# SCH_RFID-esp32-design_2024-09-27.net
KiCad netlist of a schematic drawn in EasyEDA
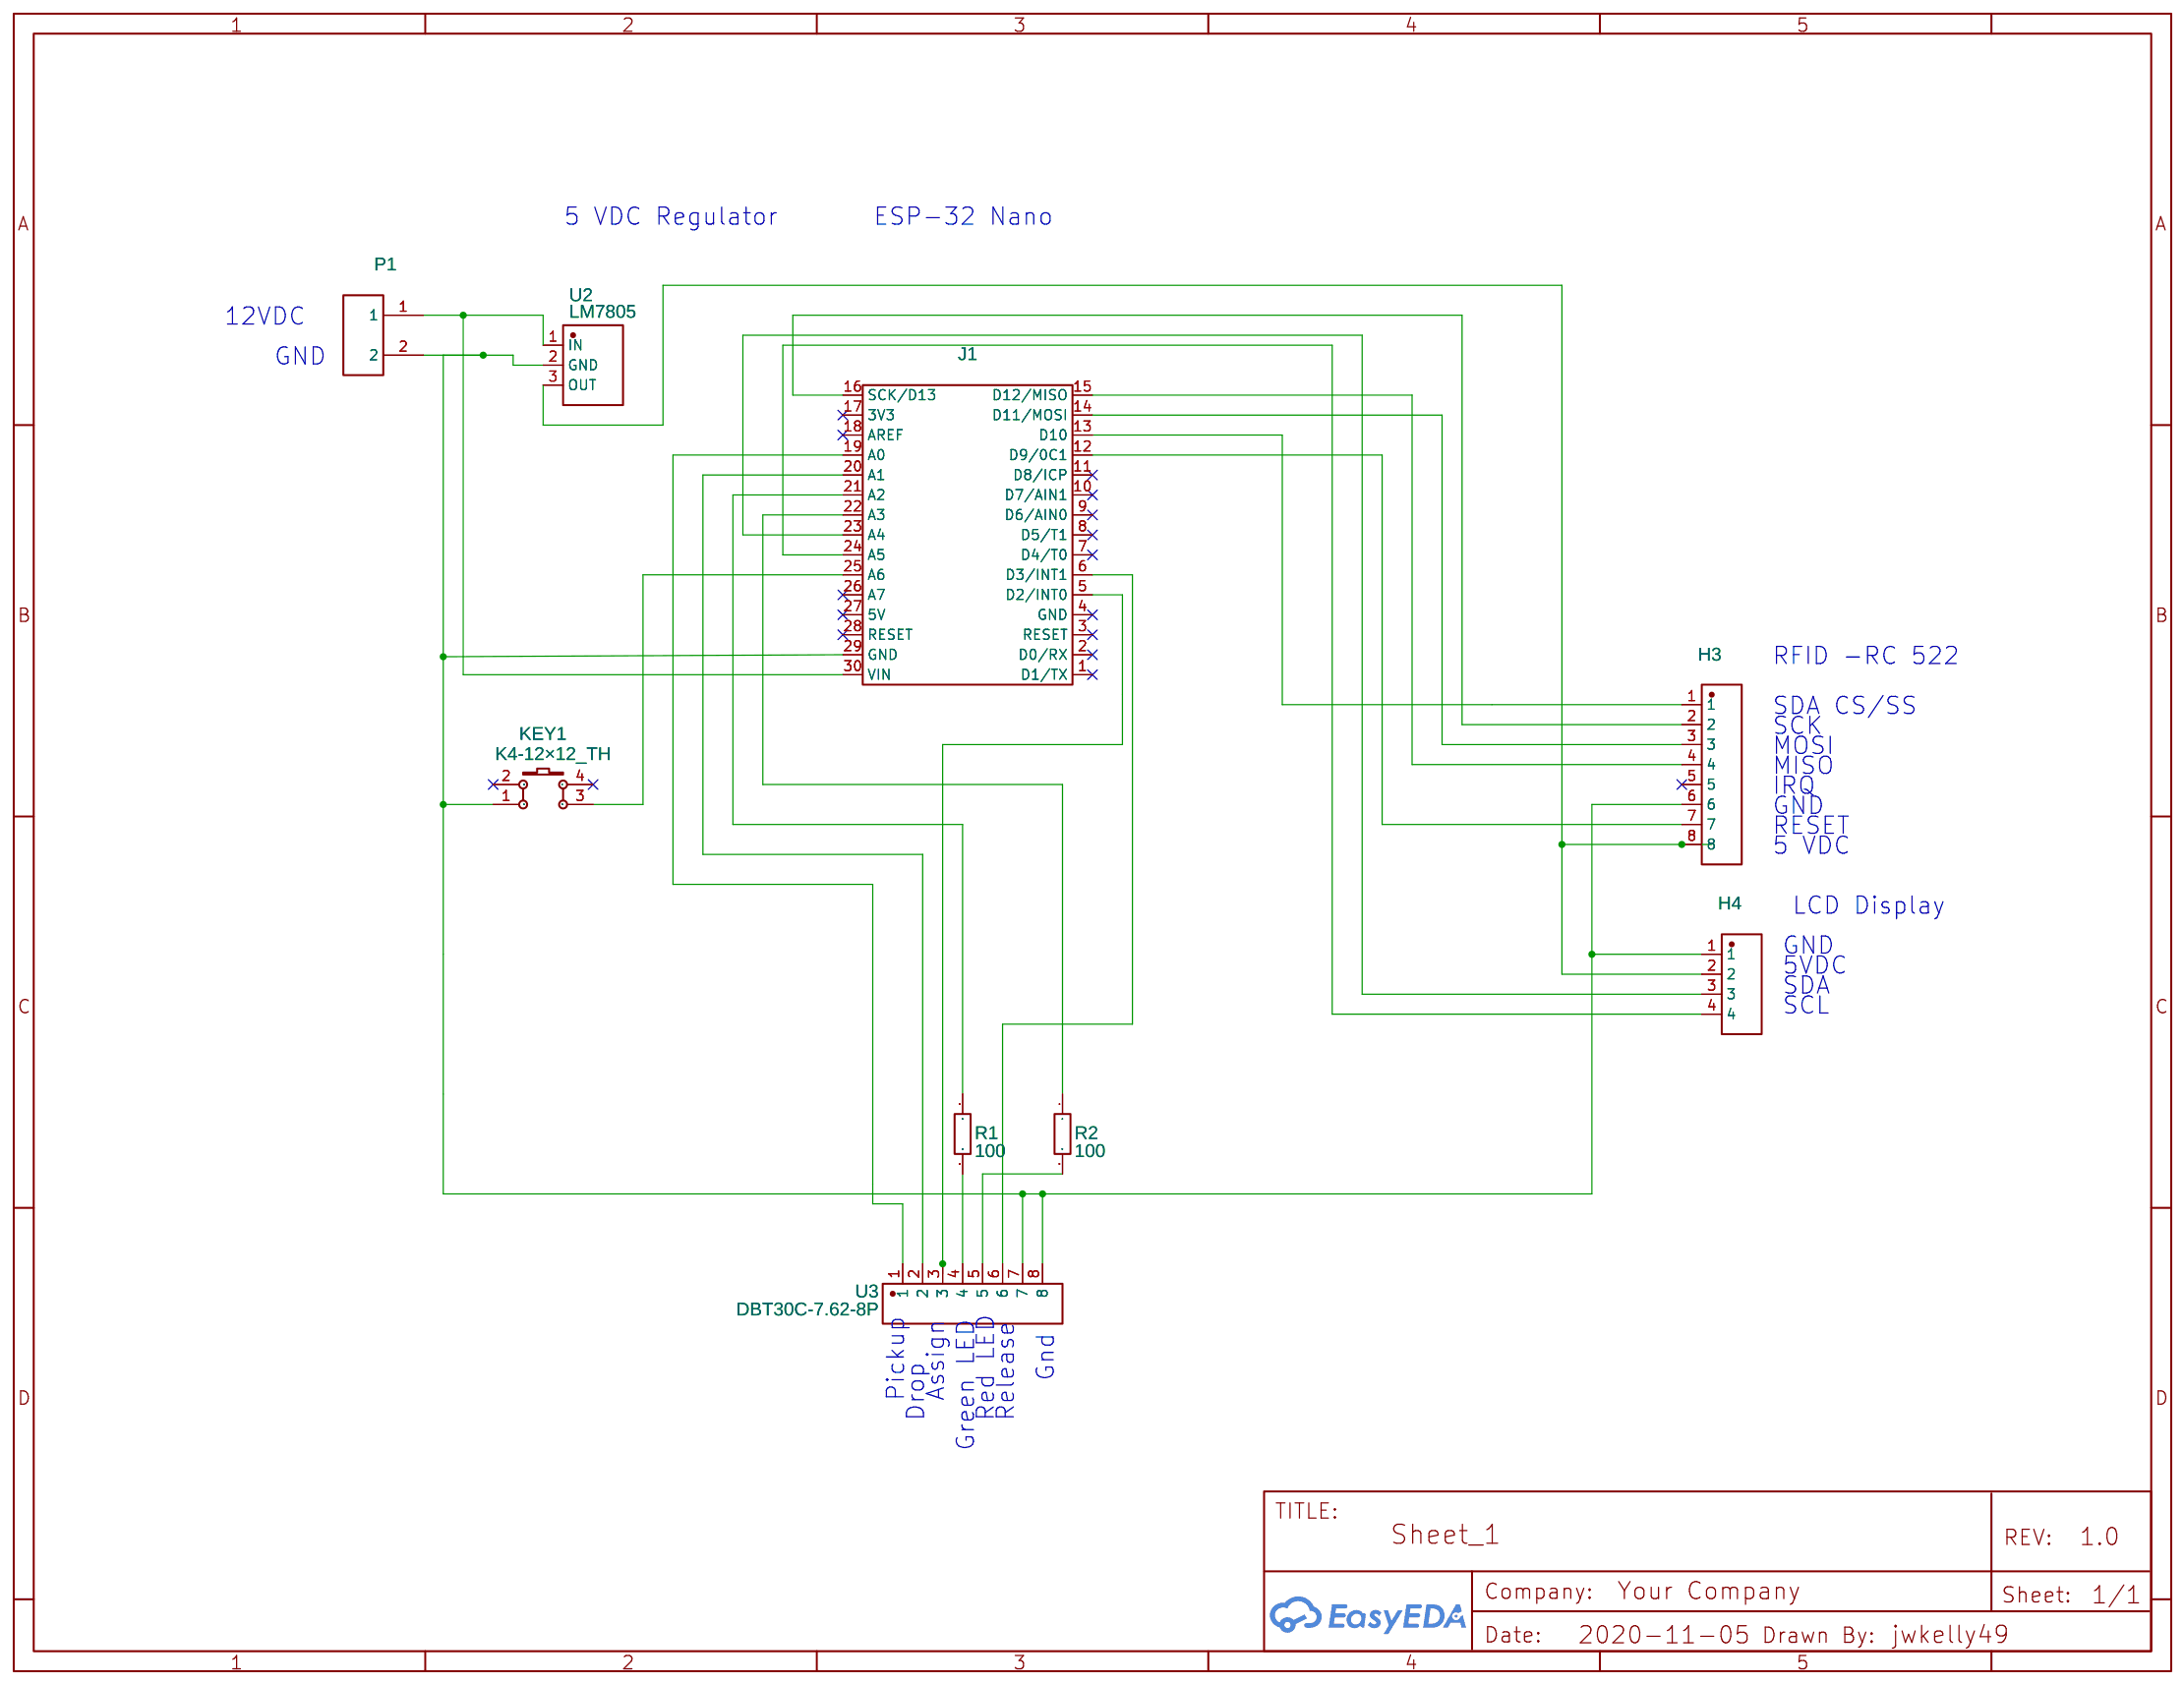
[diagram p0: schematic sheet]

(export (version "E")
  (design (tool "Eeschema 10.0.6"))
  (components
    (comp (ref "H3")
      (value "MTB125-1108R1")
      (fields (field (name "Manufacturer") "MINTRON"))
      (libsource (lib "") (part "MTB125-1108R1"))
    )
    (comp (ref "H4")
      (value "PZ254R-11-04P")
      (fields (field (name "Manufacturer") "XFCN"))
      (libsource (lib "") (part "PZ254R-11-04P"))
    )
    (comp (ref "J1") (value "Arduino_Nano_Header") (libsource (lib "") (part "Unknown_475_-545")))
    (comp (ref "KEY1")
      (value "K4-12×12_TH")
      (fields (field (name "Manufacturer Part") "K2-1103DP-M4SW-04") (field (name "Manufacturer") "韩国韩荣"))
      (libsource (lib "") (part "K4-12×12_TH"))
    )
    (comp (ref "P1")
      (value "WJ45C-B-2P")
      (fields (field (name "Manufacturer") "ReliaPro"))
      (libsource (lib "") (part "WJ45C-B-2P"))
    )
    (comp (ref "R1")
      (value "100")
      (fields (field (name "Manufacturer Part") "CFR02SJ0101A10") (field (name "Manufacturer") "UniOhm"))
      (libsource (lib "") (part "CF1/4W-100Ω±5% T52"))
    )
    (comp (ref "R2")
      (value "100")
      (fields (field (name "Manufacturer Part") "CFR02SJ0101A10") (field (name "Manufacturer") "UniOhm"))
      (libsource (lib "") (part "CF1/4W-100Ω±5% T52"))
    )
    (comp (ref "U2")
      (value "LM7805")
      (fields (field (name "Manufacturer") "TF"))
      (libsource (lib "") (part "LM7805"))
    )
    (comp (ref "U3")
      (value "DBT30C-7.62-8P")
      (fields
        (field (name "Manufacturer Part") "DBT30C-7.62-8P-BK-P")
        (field (name "Manufacturer") "DORABO(地博电气)")
      )
      (libsource (lib "") (part "DBT30C-7.62-8P"))
    )
  )
  (nets
    (net (code "1") (name "Net-(J1-A0)") (class "Default")
      (node (ref "J1") (pin "19") (pinfunction "A0_19") (pintype "unspecified"))
      (node (ref "U3") (pin "1") (pinfunction "1_1") (pintype "unspecified"))
    )
    (net (code "2") (name "Net-(J1-A1)") (class "Default")
      (node (ref "J1") (pin "20") (pinfunction "A1_20") (pintype "unspecified"))
      (node (ref "U3") (pin "2") (pinfunction "2_2") (pintype "unspecified"))
    )
    (net (code "3") (name "Net-(J1-A2)") (class "Default")
      (node (ref "J1") (pin "21") (pinfunction "A2_21") (pintype "unspecified"))
      (node (ref "R1") (pin "1") (pinfunction "1_1") (pintype "unspecified"))
    )
    (net (code "4") (name "Net-(J1-A3)") (class "Default")
      (node (ref "J1") (pin "22") (pinfunction "A3_22") (pintype "unspecified"))
      (node (ref "R2") (pin "1") (pinfunction "1_1") (pintype "unspecified"))
    )
    (net (code "5") (name "Net-(J1-A4)") (class "Default")
      (node (ref "H4") (pin "3") (pinfunction "3_3") (pintype "unspecified"))
      (node (ref "J1") (pin "23") (pinfunction "A4_23") (pintype "unspecified"))
    )
    (net (code "6") (name "Net-(J1-A5)") (class "Default")
      (node (ref "H4") (pin "4") (pinfunction "4_4") (pintype "unspecified"))
      (node (ref "J1") (pin "24") (pinfunction "A5_24") (pintype "unspecified"))
    )
    (net (code "7") (name "Net-(J1-A6)") (class "Default")
      (node (ref "J1") (pin "25") (pinfunction "A6_25") (pintype "unspecified"))
      (node (ref "KEY1") (pin "3") (pinfunction "3_3") (pintype "unspecified"))
    )
    (net (code "8") (name "Net-(J1-D2{slash}INT0)") (class "Default")
      (node (ref "J1") (pin "5") (pinfunction "D2/INT0_5") (pintype "unspecified"))
      (node (ref "U3") (pin "3") (pinfunction "3_3") (pintype "unspecified"))
    )
    (net (code "9") (name "Net-(J1-D3{slash}INT1)") (class "Default")
      (node (ref "J1") (pin "6") (pinfunction "D3/INT1_6") (pintype "unspecified"))
      (node (ref "U3") (pin "6") (pinfunction "6_6") (pintype "unspecified"))
    )
    (net (code "10") (name "Net-(J1-D9{slash}0C1)") (class "Default")
      (node (ref "H3") (pin "7") (pinfunction "7_7") (pintype "unspecified"))
      (node (ref "J1") (pin "12") (pinfunction "D9/0C1_12") (pintype "unspecified"))
    )
    (net (code "11") (name "Net-(J1-D10)") (class "Default")
      (node (ref "H3") (pin "1") (pinfunction "1_1") (pintype "unspecified"))
      (node (ref "J1") (pin "13") (pinfunction "D10_13") (pintype "unspecified"))
    )
    (net (code "12") (name "Net-(J1-D11{slash}MOSI)") (class "Default")
      (node (ref "H3") (pin "3") (pinfunction "3_3") (pintype "unspecified"))
      (node (ref "J1") (pin "14") (pinfunction "D11/MOSI_14") (pintype "unspecified"))
    )
    (net (code "13") (name "Net-(J1-D12{slash}MISO)") (class "Default")
      (node (ref "H3") (pin "4") (pinfunction "4_4") (pintype "unspecified"))
      (node (ref "J1") (pin "15") (pinfunction "D12/MISO_15") (pintype "unspecified"))
    )
    (net (code "14") (name "Net-(J1-SCK{slash}D13)") (class "Default")
      (node (ref "H3") (pin "2") (pinfunction "2_2") (pintype "unspecified"))
      (node (ref "J1") (pin "16") (pinfunction "SCK/D13_16") (pintype "unspecified"))
    )
    (net (code "15") (name "Net-(J1-VIN)") (class "Default")
      (node (ref "J1") (pin "30") (pinfunction "VIN_30") (pintype "unspecified"))
      (node (ref "P1") (pin "1") (pinfunction "1_1") (pintype "unspecified"))
      (node (ref "U2") (pin "1") (pinfunction "IN_1") (pintype "unspecified"))
    )
    (net (code "16") (name "Net-(R1-Pad2)") (class "Default")
      (node (ref "R1") (pin "2") (pinfunction "2_2") (pintype "unspecified"))
      (node (ref "U3") (pin "4") (pinfunction "4_4") (pintype "unspecified"))
    )
    (net (code "17") (name "Net-(R2-Pad2)") (class "Default")
      (node (ref "R2") (pin "2") (pinfunction "2_2") (pintype "unspecified"))
      (node (ref "U3") (pin "5") (pinfunction "5_5") (pintype "unspecified"))
    )
    (net (code "18") (name "Net-(U2-GND)") (class "Default")
      (node (ref "H3") (pin "6") (pinfunction "6_6") (pintype "unspecified"))
      (node (ref "H4") (pin "1") (pinfunction "1_1") (pintype "unspecified"))
      (node (ref "J1") (pin "29") (pinfunction "GND_29") (pintype "unspecified"))
      (node (ref "KEY1") (pin "1") (pinfunction "1_1") (pintype "unspecified"))
      (node (ref "P1") (pin "2") (pinfunction "2_2") (pintype "unspecified"))
      (node (ref "U2") (pin "2") (pinfunction "GND_2") (pintype "unspecified"))
      (node (ref "U3") (pin "7") (pinfunction "7_7") (pintype "unspecified"))
      (node (ref "U3") (pin "8") (pinfunction "8_8") (pintype "unspecified"))
    )
    (net (code "19") (name "Net-(U2-OUT)") (class "Default")
      (node (ref "H3") (pin "8") (pinfunction "8_8") (pintype "unspecified"))
      (node (ref "H4") (pin "2") (pinfunction "2_2") (pintype "unspecified"))
      (node (ref "U2") (pin "3") (pinfunction "OUT_3") (pintype "unspecified"))
    )
    (net (code "20") (name "unconnected-(H3-Pad5)") (class "Default")
      (node (ref "H3") (pin "5") (pinfunction "5_5") (pintype "unspecified+no_connect"))
    )
    (net (code "21") (name "unconnected-(J1-3V3-Pad17)") (class "Default")
      (node (ref "J1") (pin "17") (pinfunction "3V3_17") (pintype "unspecified+no_connect"))
    )
    (net (code "22") (name "unconnected-(J1-5V-Pad27)") (class "Default")
      (node (ref "J1") (pin "27") (pinfunction "5V_27") (pintype "unspecified+no_connect"))
    )
    (net (code "23") (name "unconnected-(J1-A7-Pad26)") (class "Default")
      (node (ref "J1") (pin "26") (pinfunction "A7_26") (pintype "unspecified+no_connect"))
    )
    (net (code "24") (name "unconnected-(J1-AREF-Pad18)") (class "Default")
      (node (ref "J1") (pin "18") (pinfunction "AREF_18") (pintype "unspecified+no_connect"))
    )
    (net (code "25") (name "unconnected-(J1-D0{slash}RX-Pad2)") (class "Default")
      (node (ref "J1") (pin "2") (pinfunction "D0/RX_2") (pintype "unspecified+no_connect"))
    )
    (net (code "26") (name "unconnected-(J1-D1{slash}TX-Pad1)") (class "Default")
      (node (ref "J1") (pin "1") (pinfunction "D1/TX_1") (pintype "unspecified+no_connect"))
    )
    (net (code "27") (name "unconnected-(J1-D4{slash}T0-Pad7)") (class "Default")
      (node (ref "J1") (pin "7") (pinfunction "D4/T0_7") (pintype "unspecified+no_connect"))
    )
    (net (code "28") (name "unconnected-(J1-D5{slash}T1-Pad8)") (class "Default")
      (node (ref "J1") (pin "8") (pinfunction "D5/T1_8") (pintype "unspecified+no_connect"))
    )
    (net (code "29") (name "unconnected-(J1-D6{slash}AIN0-Pad9)") (class "Default")
      (node (ref "J1") (pin "9") (pinfunction "D6/AIN0_9") (pintype "unspecified+no_connect"))
    )
    (net (code "30") (name "unconnected-(J1-D7{slash}AIN1-Pad10)") (class "Default")
      (node (ref "J1") (pin "10") (pinfunction "D7/AIN1_10") (pintype "unspecified+no_connect"))
    )
    (net (code "31") (name "unconnected-(J1-D8{slash}ICP-Pad11)") (class "Default")
      (node (ref "J1") (pin "11") (pinfunction "D8/ICP_11") (pintype "unspecified+no_connect"))
    )
    (net (code "32") (name "unconnected-(J1-GND-Pad4)") (class "Default")
      (node (ref "J1") (pin "4") (pinfunction "GND_4") (pintype "unspecified+no_connect"))
    )
    (net (code "33") (name "unconnected-(J1-RESET-Pad3)") (class "Default")
      (node (ref "J1") (pin "3") (pinfunction "RESET_3") (pintype "unspecified+no_connect"))
    )
    (net (code "34") (name "unconnected-(J1-RESET-Pad28)") (class "Default")
      (node (ref "J1") (pin "28") (pinfunction "RESET_28") (pintype "unspecified+no_connect"))
    )
    (net (code "35") (name "unconnected-(KEY1-Pad2)") (class "Default")
      (node (ref "KEY1") (pin "2") (pinfunction "2_2") (pintype "unspecified+no_connect"))
    )
    (net (code "36") (name "unconnected-(KEY1-Pad4)") (class "Default")
      (node (ref "KEY1") (pin "4") (pinfunction "4_4") (pintype "unspecified+no_connect"))
    )
  )
)
